# Active_Electrode.net
KiCad netlist of a schematic drawn in Altium Designer
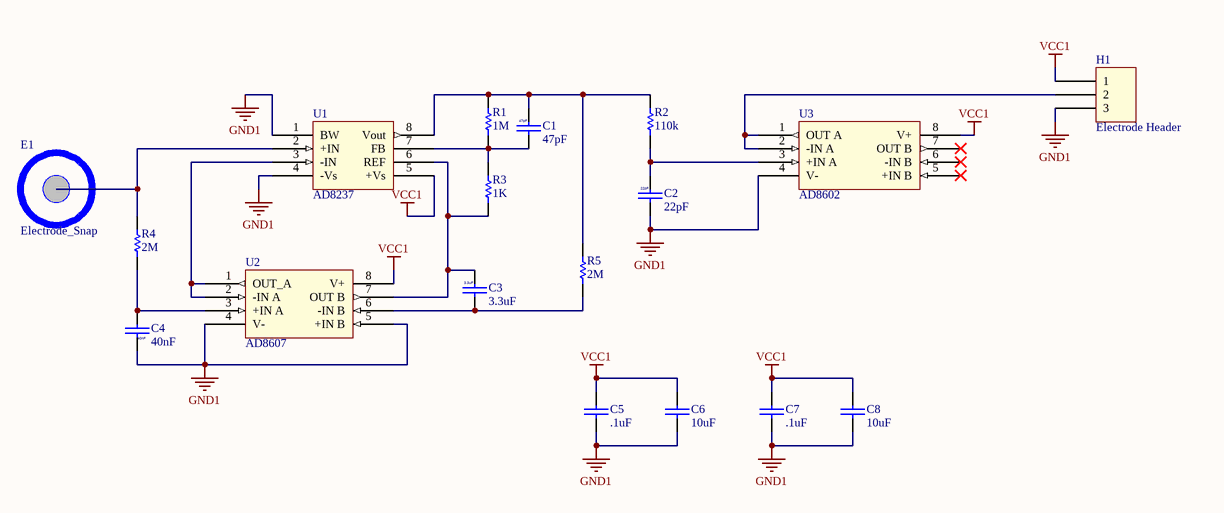
[diagram p0: Active_Electrode.SchDoc]

(export (version "E")
  (design (tool "Eeschema 10.0.6"))
  (components
    (comp (ref "C1")
      (value "47pF")
      (footprint "0402[IMP]")
      (fields (field (name "VOLTAGE") "CMAX") (field (name "ALTIUM_VALUE") "47pF"))
      (libsource (lib "Biosense_Altium_Library") (part "CAPACITOR"))
    )
    (comp (ref "C2")
      (value "22pF")
      (footprint "0402[IMP]")
      (fields (field (name "VOLTAGE") "CMAX") (field (name "ALTIUM_VALUE") "22pF"))
      (libsource (lib "Biosense_Altium_Library") (part "CAPACITOR"))
    )
    (comp (ref "C3")
      (value "3.3uF")
      (footprint "0402[IMP]")
      (fields (field (name "VOLTAGE") "CMAX") (field (name "ALTIUM_VALUE") "3.3uF"))
      (libsource (lib "Biosense_Altium_Library") (part "CAPACITOR"))
    )
    (comp (ref "C4")
      (value "40nF")
      (footprint "0402[IMP]")
      (fields (field (name "VOLTAGE") "CMAX") (field (name "ALTIUM_VALUE") "40nF"))
      (libsource (lib "Biosense_Altium_Library") (part "CAPACITOR"))
    )
    (comp (ref "C5")
      (value ".1uF")
      (footprint "0402[IMP]")
      (fields (field (name "VOLTAGE") "CMAX"))
      (libsource (lib "Biosense_Altium_Library") (part "CAPACITOR"))
    )
    (comp (ref "C6")
      (value "10uF")
      (footprint "0402[IMP]")
      (fields (field (name "VOLTAGE") "CMAX"))
      (libsource (lib "Biosense_Altium_Library") (part "CAPACITOR"))
    )
    (comp (ref "C7")
      (value ".1uF")
      (footprint "0402[IMP]")
      (fields (field (name "VOLTAGE") "CMAX"))
      (libsource (lib "Biosense_Altium_Library") (part "CAPACITOR"))
    )
    (comp (ref "C8")
      (value "10uF")
      (footprint "0402[IMP]")
      (fields (field (name "VOLTAGE") "CMAX"))
      (libsource (lib "Biosense_Altium_Library") (part "CAPACITOR"))
    )
    (comp (ref "E1")
      (value "Electrode_Snap")
      (footprint "Electrode_Socket")
      (libsource (lib "Biosense_Altium_Library") (part "Electrode_Snap"))
    )
    (comp (ref "H1")
      (value "Electrode Header")
      (footprint "Electrode Header")
      (libsource (lib "Biosense_Altium_Library") (part "Electrode Header"))
    )
    (comp (ref "R1")
      (value "1M")
      (footprint "0402[IMP]")
      (libsource (lib "Biosense_Altium_Library") (part "RESISTOR"))
    )
    (comp (ref "R2")
      (value "110k")
      (footprint "0402[IMP]")
      (libsource (lib "Biosense_Altium_Library") (part "RESISTOR"))
    )
    (comp (ref "R3")
      (value "1K")
      (footprint "0402[IMP]")
      (libsource (lib "Biosense_Altium_Library") (part "RESISTOR"))
    )
    (comp (ref "R4")
      (value "2M")
      (footprint "0402[IMP]")
      (libsource (lib "Biosense_Altium_Library") (part "RESISTOR"))
    )
    (comp (ref "R5")
      (value "2M")
      (footprint "0402[IMP]")
      (libsource (lib "Biosense_Altium_Library") (part "RESISTOR"))
    )
    (comp (ref "U1")
      (value "AD8237")
      (footprint "MSOP-8")
      (libsource (lib "Biosense_Altium_Library") (part "AD8237"))
    )
    (comp (ref "U2")
      (value "AD8607")
      (footprint "MSOP-8")
      (libsource (lib "Biosense_Altium_Library") (part "AD8607"))
    )
    (comp (ref "U3")
      (value "AD8602")
      (footprint "MSOP-8")
      (libsource (lib "Biosense_Altium_Library") (part "AD8602"))
    )
  )
  (nets
    (net (code "1") (name "GND1") (class "Default")
      (node (ref "C2") (pin "1") (pinfunction "1_1") (pintype "passive"))
      (node (ref "C4") (pin "2") (pinfunction "2_2") (pintype "passive"))
      (node (ref "C5") (pin "1") (pinfunction "1_1") (pintype "passive"))
      (node (ref "C6") (pin "1") (pinfunction "1_1") (pintype "passive"))
      (node (ref "C7") (pin "1") (pinfunction "1_1") (pintype "passive"))
      (node (ref "C8") (pin "1") (pinfunction "1_1") (pintype "passive"))
      (node (ref "H1") (pin "3") (pinfunction "3_3") (pintype "passive"))
      (node (ref "U1") (pin "1") (pinfunction "BW_1") (pintype "passive"))
      (node (ref "U1") (pin "4") (pinfunction "-Vs_4") (pintype "power_in"))
      (node (ref "U2") (pin "4") (pinfunction "V-_4") (pintype "power_in"))
      (node (ref "U2") (pin "5") (pinfunction "+IN_B_5") (pintype "input"))
      (node (ref "U3") (pin "4") (pinfunction "V-_4") (pintype "power_in"))
    )
    (net (code "2") (name "Net-(E1-Signal)") (class "Default")
      (node (ref "E1") (pin "1") (pinfunction "Signal_1") (pintype "passive"))
      (node (ref "R4") (pin "2") (pinfunction "2_2") (pintype "passive"))
      (node (ref "U1") (pin "2") (pinfunction "+IN_2") (pintype "input"))
    )
    (net (code "3") (name "Net-(U1--IN)") (class "Default")
      (node (ref "U1") (pin "3") (pinfunction "-IN_3") (pintype "input"))
      (node (ref "U2") (pin "1") (pinfunction "OUT_A_1") (pintype "output"))
      (node (ref "U2") (pin "2") (pinfunction "-IN_A_2") (pintype "input"))
    )
    (net (code "4") (name "Net-(U1-FB)") (class "Default")
      (node (ref "C1") (pin "1") (pinfunction "1_1") (pintype "passive"))
      (node (ref "R1") (pin "1") (pinfunction "1_1") (pintype "passive"))
      (node (ref "R3") (pin "2") (pinfunction "2_2") (pintype "passive"))
      (node (ref "U1") (pin "7") (pinfunction "FB_7") (pintype "passive"))
    )
    (net (code "5") (name "Net-(U1-REF)") (class "Default")
      (node (ref "C3") (pin "2") (pinfunction "2_2") (pintype "passive"))
      (node (ref "R3") (pin "1") (pinfunction "1_1") (pintype "passive"))
      (node (ref "U1") (pin "6") (pinfunction "REF_6") (pintype "passive"))
      (node (ref "U2") (pin "7") (pinfunction "OUT_B_7") (pintype "output"))
    )
    (net (code "6") (name "Net-(U1-Vout)") (class "Default")
      (node (ref "C1") (pin "2") (pinfunction "2_2") (pintype "passive"))
      (node (ref "R1") (pin "2") (pinfunction "2_2") (pintype "passive"))
      (node (ref "R2") (pin "2") (pinfunction "2_2") (pintype "passive"))
      (node (ref "R5") (pin "2") (pinfunction "2_2") (pintype "passive"))
      (node (ref "U1") (pin "8") (pinfunction "Vout_8") (pintype "output"))
    )
    (net (code "7") (name "Net-(U2-+IN_A)") (class "Default")
      (node (ref "C4") (pin "1") (pinfunction "1_1") (pintype "passive"))
      (node (ref "R4") (pin "1") (pinfunction "1_1") (pintype "passive"))
      (node (ref "U2") (pin "3") (pinfunction "+IN_A_3") (pintype "input"))
    )
    (net (code "8") (name "Net-(U2--IN_B)") (class "Default")
      (node (ref "C3") (pin "1") (pinfunction "1_1") (pintype "passive"))
      (node (ref "R5") (pin "1") (pinfunction "1_1") (pintype "passive"))
      (node (ref "U2") (pin "6") (pinfunction "-IN_B_6") (pintype "input"))
    )
    (net (code "9") (name "Net-(U3-+IN_A)") (class "Default")
      (node (ref "C2") (pin "2") (pinfunction "2_2") (pintype "passive"))
      (node (ref "R2") (pin "1") (pinfunction "1_1") (pintype "passive"))
      (node (ref "U3") (pin "3") (pinfunction "+IN_A_3") (pintype "input"))
    )
    (net (code "10") (name "Net-(U3--IN_A)") (class "Default")
      (node (ref "H1") (pin "2") (pinfunction "2_2") (pintype "passive"))
      (node (ref "U3") (pin "1") (pinfunction "OUT_A_1") (pintype "output"))
      (node (ref "U3") (pin "2") (pinfunction "-IN_A_2") (pintype "input"))
    )
    (net (code "11") (name "VCC1") (class "Default")
      (node (ref "C5") (pin "2") (pinfunction "2_2") (pintype "passive"))
      (node (ref "C6") (pin "2") (pinfunction "2_2") (pintype "passive"))
      (node (ref "C7") (pin "2") (pinfunction "2_2") (pintype "passive"))
      (node (ref "C8") (pin "2") (pinfunction "2_2") (pintype "passive"))
      (node (ref "H1") (pin "1") (pinfunction "1_1") (pintype "passive"))
      (node (ref "U1") (pin "5") (pinfunction "+Vs_5") (pintype "power_in"))
      (node (ref "U2") (pin "8") (pinfunction "V+_8") (pintype "power_in"))
      (node (ref "U3") (pin "8") (pinfunction "V+_8") (pintype "power_in"))
    )
    (net (code "12") (name "unconnected-(U3-+IN_B-Pad5)") (class "Default")
      (node (ref "U3") (pin "5") (pinfunction "+IN_B_5") (pintype "input+no_connect"))
    )
    (net (code "13") (name "unconnected-(U3--IN_B-Pad6)") (class "Default")
      (node (ref "U3") (pin "6") (pinfunction "-IN_B_6") (pintype "input+no_connect"))
    )
    (net (code "14") (name "unconnected-(U3-OUT_B-Pad7)") (class "Default")
      (node (ref "U3") (pin "7") (pinfunction "OUT_B_7") (pintype "output+no_connect"))
    )
  )
)
